# Antena.net
KiCad netlist of a schematic drawn in Altium Designer
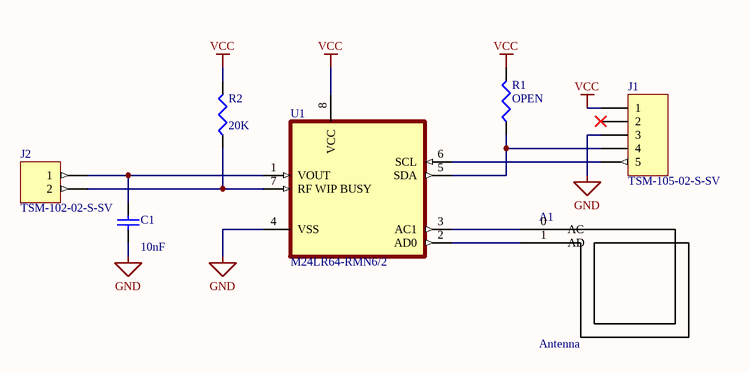
[diagram p0: Antena.SchDoc]

(export (version "E")
  (design (tool "Eeschema 10.0.6"))
  (components
    (comp (ref "A1") (value "Antenna") (footprint "Antenna1") (libsource (lib "Schlib1") (part "Antenna")))
    (comp (ref "C1")
      (value "10nF")
      (footprint "C1206")
      (description "Capacitor (Semiconductor SIM Model)")
      (fields (field (name "Comment") "Cap Semi") (field (name "PUBLISHER") "Altium Limited"))
      (libsource (lib "Miscellaneous Devices") (part "Cap Semi"))
    )
    (comp (ref "J1")
      (value "TSM-105-02-S-SV")
      (footprint "HDR1X5")
      (fields (field (name "PUBLISHER") "Altium Limited"))
      (libsource (lib "Miscellaneous Connectors") (part "Header 5"))
    )
    (comp (ref "J2")
      (value "TSM-102-02-S-SV")
      (footprint "HDR1X2")
      (description "Header, 2-Pin")
      (fields (field (name "PUBLISHER") "Altium Limited"))
      (libsource (lib "Miscellaneous Connectors") (part "Header 2"))
    )
    (comp (ref "R1")
      (value "OPEN")
      (footprint "J1-0603")
      (description "Resistor")
      (fields (field (name "PUBLISHER") "Altium Limited"))
      (libsource (lib "Miscellaneous Devices") (part "Res3"))
    )
    (comp (ref "R2")
      (value "20K")
      (footprint "J1-0603")
      (description "Resistor")
      (fields (field (name "PUBLISHER") "Altium Limited"))
      (libsource (lib "Miscellaneous Devices") (part "Res3"))
    )
    (comp (ref "U1")
      (value "M24LR64-RMN6/2")
      (footprint "SOIC127P600X175-8N")
      (description "64 Kbit EEPROM")
      (fields (field (name "MP") "M24LR64-RMN6-2"))
      (libsource (lib "M24LR64-RMN6_2") (part "M24LR64-RMN6/2"))
    )
  )
  (nets
    (net (code "1") (name "GND") (class "Default")
      (node (ref "C1") (pin "1") (pinfunction "1_1") (pintype "passive"))
      (node (ref "J1") (pin "3") (pinfunction "3_3") (pintype "passive"))
      (node (ref "U1") (pin "4") (pinfunction "VSS_4") (pintype "power_in"))
    )
    (net (code "2") (name "Net-(A1-AC)") (class "Default")
      (node (ref "A1") (pin "0") (pinfunction "AC_0") (pintype "passive"))
      (node (ref "U1") (pin "3") (pinfunction "AC1_3") (pintype "output"))
    )
    (net (code "3") (name "Net-(A1-AD)") (class "Default")
      (node (ref "A1") (pin "1") (pinfunction "AD_1") (pintype "passive"))
      (node (ref "U1") (pin "2") (pinfunction "AD0_2") (pintype "output"))
    )
    (net (code "4") (name "Net-(U1-RF_WIP_BUSY)") (class "Default")
      (node (ref "J2") (pin "2") (pinfunction "2_2") (pintype "output"))
      (node (ref "R2") (pin "1") (pinfunction "1_1") (pintype "passive"))
      (node (ref "U1") (pin "7") (pinfunction "RF_WIP_BUSY_7") (pintype "input"))
    )
    (net (code "5") (name "Net-(U1-SCL)") (class "Default")
      (node (ref "J1") (pin "5") (pinfunction "5_5") (pintype "output"))
      (node (ref "U1") (pin "6") (pinfunction "SCL_6") (pintype "input"))
    )
    (net (code "6") (name "Net-(U1-SDA)") (class "Default")
      (node (ref "J1") (pin "4") (pinfunction "4_4") (pintype "passive"))
      (node (ref "R1") (pin "1") (pinfunction "1_1") (pintype "passive"))
      (node (ref "U1") (pin "5") (pinfunction "SDA_5") (pintype "output"))
    )
    (net (code "7") (name "Net-(U1-VOUT)") (class "Default")
      (node (ref "C1") (pin "2") (pinfunction "2_2") (pintype "passive"))
      (node (ref "J2") (pin "1") (pinfunction "1_1") (pintype "output"))
      (node (ref "U1") (pin "1") (pinfunction "VOUT_1") (pintype "input"))
    )
    (net (code "8") (name "VCC") (class "Default")
      (node (ref "J1") (pin "1") (pinfunction "1_1") (pintype "passive"))
      (node (ref "R1") (pin "2") (pinfunction "2_2") (pintype "passive"))
      (node (ref "R2") (pin "2") (pinfunction "2_2") (pintype "passive"))
      (node (ref "U1") (pin "8") (pinfunction "VCC_8") (pintype "power_in"))
    )
    (net (code "9") (name "unconnected-(J1-Pad2)") (class "Default")
      (node (ref "J1") (pin "2") (pinfunction "2_2") (pintype "passive+no_connect"))
    )
  )
)
